# Sensor_Module.net
KiCad netlist of a schematic drawn in Altium Designer
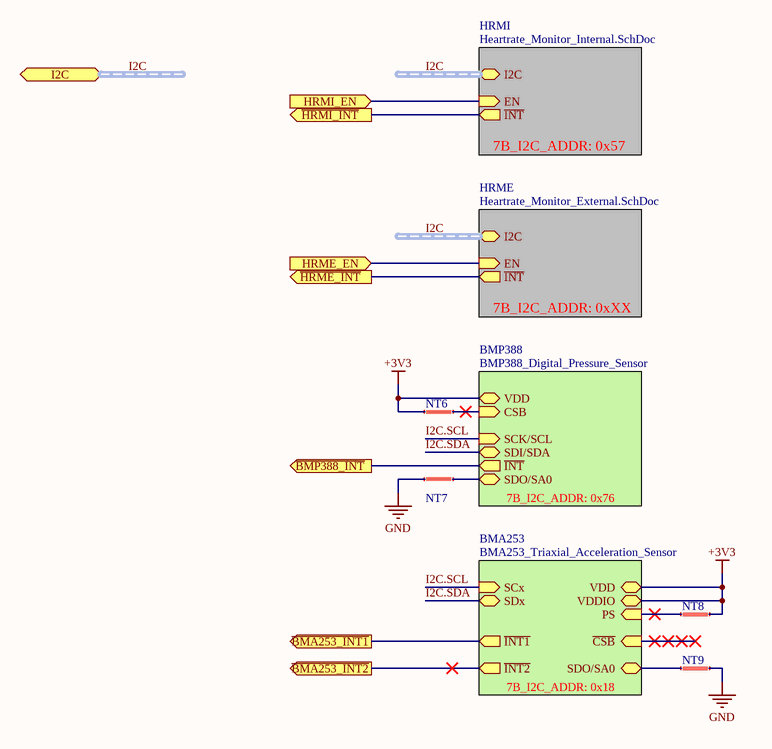
[diagram p0: Sensor_Module.SchDoc]

(export (version "E")
  (design (tool "Eeschema 10.0.6"))
  (components
    (comp (ref "NT6")
      (value "Net Tie")
      (footprint "Net Tie 6x30mil")
      (libsource (lib "BLDC_Motor_Driver") (part "Net Tie Line"))
    )
    (comp (ref "NT7")
      (value "Net Tie")
      (footprint "Net Tie 6x30mil")
      (libsource (lib "") (part "Net Tie Line_1"))
    )
    (comp (ref "NT8")
      (value "Net Tie")
      (footprint "Net Tie 6x30mil")
      (libsource (lib "BLDC_Motor_Driver") (part "Net Tie Line"))
    )
    (comp (ref "NT9")
      (value "Net Tie")
      (footprint "Net Tie 6x30mil")
      (libsource (lib "BLDC_Motor_Driver") (part "Net Tie Line"))
    )
  )
  (nets
    (net (code "2") (name "+3V3") (class "Default")
      (node (ref "NT6") (pin "1") (pintype "passive"))
      (node (ref "NT8") (pin "2") (pintype "passive"))
    )
    (net (code "6") (name "/CSB") (class "Default") (node (ref "NT6") (pin "2") (pintype "passive")))
    (net (code "14") (name "/PS") (class "Default") (node (ref "NT8") (pin "1") (pintype "passive")))
    (net (code "15") (name "/SDO{slash}SA0") (class "Default")
      (node (ref "NT7") (pin "1") (pintype "passive"))
    )
    (net (code "16") (name "/SDO{slash}SA0_1") (class "Default")
      (node (ref "NT9") (pin "1") (pintype "passive"))
    )
    (net (code "18") (name "GND") (class "Default")
      (node (ref "NT7") (pin "2") (pintype "passive"))
      (node (ref "NT9") (pin "2") (pintype "passive"))
    )
  )
)
